# OrbiMote_v0_1.net
KiCad netlist of a schematic drawn in EAGLE
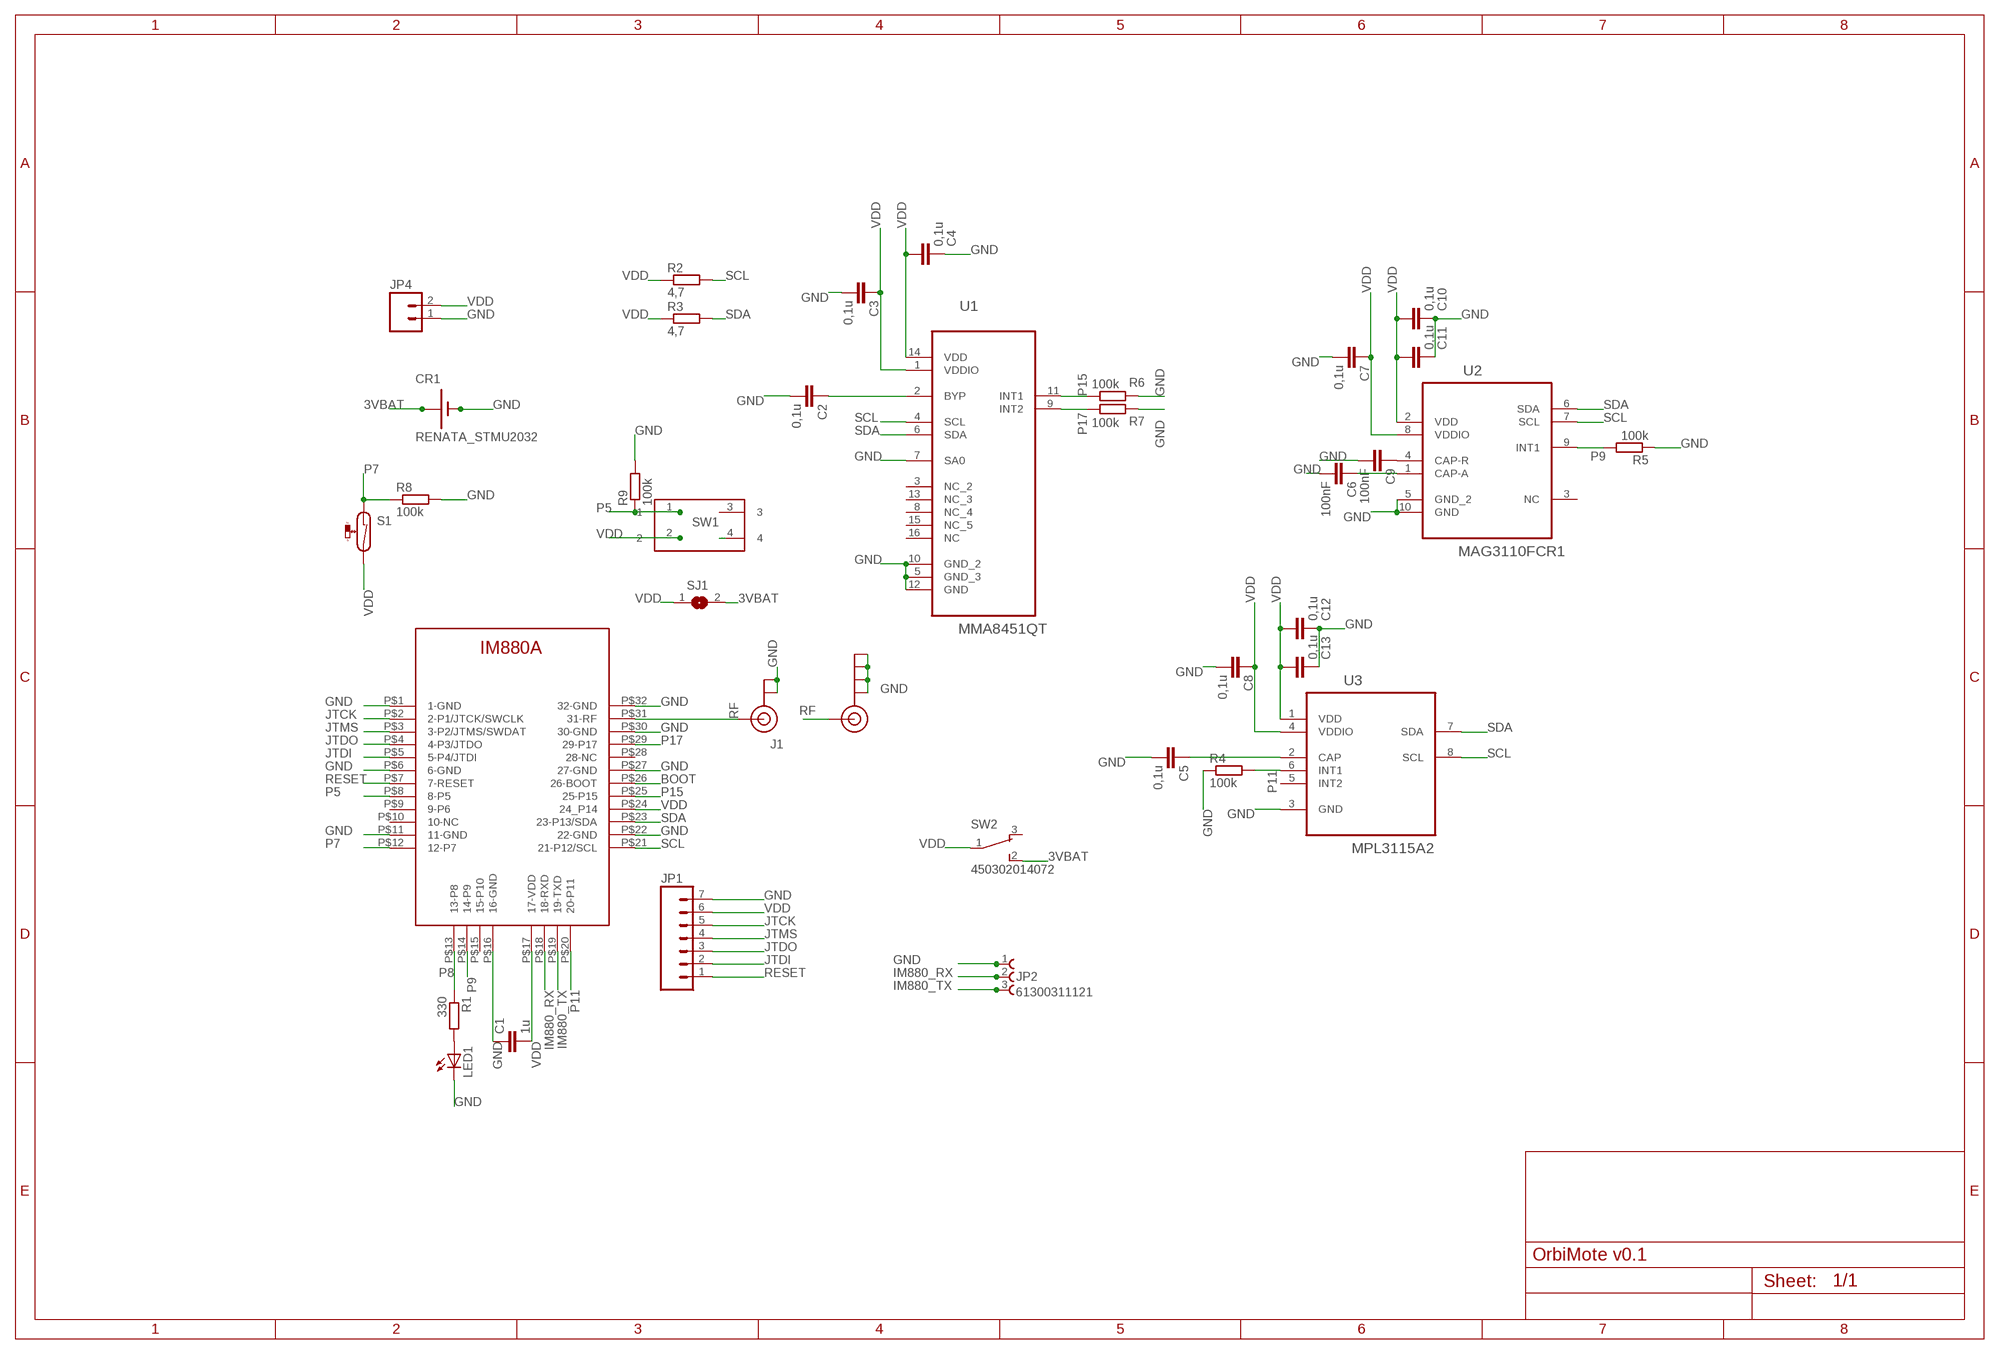
[diagram p0: schematic, sheet 1]

(export (version "E")
  (design (tool "Eeschema 10.0.6"))
  (components
    (comp (ref "C1")
      (value "1u")
      (footprint "eagle-import:C0603")
      (libsource (lib "eagle-import") (part "resistor_C-EUC0603"))
    )
    (comp (ref "C2")
      (value "0,1u")
      (footprint "eagle-import:C0603")
      (libsource (lib "eagle-import") (part "C-EUC0603"))
    )
    (comp (ref "C3")
      (value "0,1u")
      (footprint "eagle-import:C0603")
      (libsource (lib "eagle-import") (part "C-EUC0603"))
    )
    (comp (ref "C4")
      (value "0,1u")
      (footprint "eagle-import:C0603")
      (libsource (lib "eagle-import") (part "C-EUC0603"))
    )
    (comp (ref "C5")
      (value "0,1u")
      (footprint "eagle-import:C0603")
      (libsource (lib "eagle-import") (part "C-EUC0603"))
    )
    (comp (ref "C6")
      (value "100nF")
      (footprint "eagle-import:C0603")
      (libsource (lib "eagle-import") (part "C-EUC0603"))
    )
    (comp (ref "C7")
      (value "0,1u")
      (footprint "eagle-import:C0603")
      (libsource (lib "eagle-import") (part "C-EUC0603"))
    )
    (comp (ref "C8")
      (value "0,1u")
      (footprint "eagle-import:C0603")
      (libsource (lib "eagle-import") (part "C-EUC0603"))
    )
    (comp (ref "C9")
      (value "100nF")
      (footprint "eagle-import:C0603")
      (libsource (lib "eagle-import") (part "C-EUC0603"))
    )
    (comp (ref "C10")
      (value "0,1u")
      (footprint "eagle-import:C0603")
      (libsource (lib "eagle-import") (part "C-EUC0603"))
    )
    (comp (ref "C11")
      (value "0,1u")
      (footprint "eagle-import:C0603")
      (libsource (lib "eagle-import") (part "C-EUC0603"))
    )
    (comp (ref "C12")
      (value "0,1u")
      (footprint "eagle-import:C0603")
      (libsource (lib "eagle-import") (part "C-EUC0603"))
    )
    (comp (ref "C13")
      (value "0,1u")
      (footprint "eagle-import:C0603")
      (libsource (lib "eagle-import") (part "C-EUC0603"))
    )
    (comp (ref "CR1")
      (value "RENATA_STMU2032")
      (footprint "eagle-import:SMTU2032")
      (libsource (lib "eagle-import") (part "RENATA_STMU2032"))
    )
    (comp (ref "IM1")
      (value "IM880A")
      (footprint "eagle-import:IM880A")
      (libsource (lib "eagle-import") (part "IM880A"))
    )
    (comp (ref "J$1")
      (value "SMA_EDGE")
      (footprint "eagle-import:SMA-EDGE")
      (libsource (lib "eagle-import") (part "SMA_EDGE"))
    )
    (comp (ref "J1")
      (value "U.FL")
      (footprint "eagle-import:U.FL")
      (libsource (lib "eagle-import") (part "U.FL"))
    )
    (comp (ref "JP1")
      (value "M07")
      (footprint "eagle-import:1X07")
      (libsource (lib "eagle-import") (part "M07"))
    )
    (comp (ref "JP2")
      (value "61300311121")
      (footprint "eagle-import:61300311121")
      (libsource (lib "eagle-import") (part "61300311121"))
    )
    (comp (ref "JP4")
      (value "M02JST-PTH-VERT")
      (footprint "eagle-import:JST-2-PTH-VERT")
      (libsource (lib "eagle-import") (part "M02JST-PTH-VERT"))
    )
    (comp (ref "LED1")
      (value "LEDCHIPLED_0603")
      (footprint "eagle-import:CHIPLED_0603")
      (libsource (lib "eagle-import") (part "LEDCHIPLED_0603"))
    )
    (comp (ref "R1")
      (value "330")
      (footprint "eagle-import:R0603")
      (libsource (lib "eagle-import") (part "R-EU_R0603"))
    )
    (comp (ref "R2")
      (value "4,7")
      (footprint "eagle-import:R0603")
      (libsource (lib "eagle-import") (part "R-EU_R0603"))
    )
    (comp (ref "R3")
      (value "4,7")
      (footprint "eagle-import:R0603")
      (libsource (lib "eagle-import") (part "R-EU_R0603"))
    )
    (comp (ref "R4")
      (value "100k")
      (footprint "eagle-import:R0603")
      (libsource (lib "eagle-import") (part "R-EU_R0603"))
    )
    (comp (ref "R5")
      (value "100k")
      (footprint "eagle-import:R0603")
      (libsource (lib "eagle-import") (part "R-EU_R0603"))
    )
    (comp (ref "R6")
      (value "100k")
      (footprint "eagle-import:R0603")
      (libsource (lib "eagle-import") (part "R-EU_R0603"))
    )
    (comp (ref "R7")
      (value "100k")
      (footprint "eagle-import:R0603")
      (libsource (lib "eagle-import") (part "R-EU_R0603"))
    )
    (comp (ref "R8")
      (value "100k")
      (footprint "eagle-import:R0603")
      (libsource (lib "eagle-import") (part "R-EU_R0603"))
    )
    (comp (ref "R9")
      (value "100k")
      (footprint "eagle-import:R0603")
      (libsource (lib "eagle-import") (part "R-EU_R0603"))
    )
    (comp (ref "S1")
      (value "REED-SWITCH-CT10-1530-G1")
      (footprint "eagle-import:CT10-G1")
      (fields (field (name "MF") "COTO TECHNOLOGY") (field (name "MPN") "CT10-1530-G1"))
      (libsource (lib "eagle-import") (part "REED-SWITCH-CT10-1530-G1"))
    )
    (comp (ref "SJ1") (value "SJ") (footprint "eagle-import:SJ") (libsource (lib "eagle-import") (part "SJ")))
    (comp (ref "SW1")
      (value "430152043826")
      (footprint "eagle-import:430152043826")
      (libsource (lib "eagle-import") (part "430152043826"))
    )
    (comp (ref "SW2")
      (value "450302014072")
      (footprint "eagle-import:450302014072")
      (libsource (lib "eagle-import") (part "450302014072"))
    )
    (comp (ref "U1")
      (value "MMA8451QT")
      (footprint "eagle-import:QFN50P300X300X100-16N")
      (fields (field (name "MPN") "MMA8451QT "))
      (libsource (lib "eagle-import") (part "MMA8451QT"))
    )
    (comp (ref "U2")
      (value "MAG3110FCR1")
      (footprint "eagle-import:DFN200X200X90-10N")
      (libsource (lib "eagle-import") (part "MAG3110FCR1"))
    )
    (comp (ref "U3")
      (value "MPL3115A2")
      (footprint "eagle-import:DFN300X500X120-8N")
      (libsource (lib "eagle-import") (part "MPL3115A2"))
    )
  )
  (nets
    (net (code "1") (name "/3VBAT") (class "Default")
      (node (ref "CR1") (pin "+") (pinfunction "3VBAT_+") (pintype "passive"))
      (node (ref "SJ1") (pin "2") (pinfunction "2_2") (pintype "passive"))
      (node (ref "SW2") (pin "2") (pinfunction "2_2") (pintype "passive"))
    )
    (net (code "2") (name "/BOOT") (class "Default")
      (node (ref "IM1") (pin "P$26") (pinfunction "26-BOOT_P$26") (pintype "bidirectional"))
    )
    (net (code "3") (name "/GND") (class "Default")
      (node (ref "C1") (pin "1") (pinfunction "1_1") (pintype "passive"))
      (node (ref "C10") (pin "2") (pinfunction "2_2") (pintype "passive"))
      (node (ref "C11") (pin "2") (pinfunction "2_2") (pintype "passive"))
      (node (ref "C12") (pin "2") (pinfunction "2_2") (pintype "passive"))
      (node (ref "C13") (pin "2") (pinfunction "2_2") (pintype "passive"))
      (node (ref "C2") (pin "2") (pinfunction "2_2") (pintype "passive"))
      (node (ref "C3") (pin "2") (pinfunction "2_2") (pintype "passive"))
      (node (ref "C4") (pin "2") (pinfunction "2_2") (pintype "passive"))
      (node (ref "C5") (pin "2") (pinfunction "2_2") (pintype "passive"))
      (node (ref "C6") (pin "2") (pinfunction "2_2") (pintype "passive"))
      (node (ref "C7") (pin "2") (pinfunction "2_2") (pintype "passive"))
      (node (ref "C8") (pin "2") (pinfunction "2_2") (pintype "passive"))
      (node (ref "C9") (pin "2") (pinfunction "2_2") (pintype "passive"))
      (node (ref "CR1") (pin "-") (pinfunction "-_-") (pintype "passive"))
      (node (ref "IM1") (pin "P$1") (pinfunction "1-GND_P$1") (pintype "bidirectional"))
      (node (ref "IM1") (pin "P$11") (pinfunction "11-GND_P$11") (pintype "bidirectional"))
      (node (ref "IM1") (pin "P$16") (pinfunction "16-GND_P$16") (pintype "bidirectional"))
      (node (ref "IM1") (pin "P$22") (pinfunction "22-GND_P$22") (pintype "bidirectional"))
      (node (ref "IM1") (pin "P$27") (pinfunction "27-GND_P$27") (pintype "bidirectional"))
      (node (ref "IM1") (pin "P$30") (pinfunction "30-GND_P$30") (pintype "bidirectional"))
      (node (ref "IM1") (pin "P$32") (pinfunction "32-GND_P$32") (pintype "bidirectional"))
      (node (ref "IM1") (pin "P$6") (pinfunction "6-GND_P$6") (pintype "bidirectional"))
      (node (ref "J$1") (pin "GND@0") (pinfunction "GND_GND@0") (pintype "bidirectional"))
      (node (ref "J$1") (pin "GND@1") (pinfunction "GND_GND@1") (pintype "bidirectional"))
      (node (ref "J$1") (pin "GND@2") (pinfunction "GND_GND@2") (pintype "bidirectional"))
      (node (ref "J$1") (pin "GND@3") (pinfunction "GND_GND@3") (pintype "bidirectional"))
      (node (ref "J1") (pin "P$1") (pinfunction "GND_P$1") (pintype "bidirectional"))
      (node (ref "J1") (pin "P$2") (pinfunction "GND_P$2") (pintype "bidirectional"))
      (node (ref "JP1") (pin "7") (pinfunction "7_7") (pintype "passive"))
      (node (ref "JP2") (pin "1") (pinfunction "1_1") (pintype "passive"))
      (node (ref "JP4") (pin "1") (pinfunction "1_1") (pintype "passive"))
      (node (ref "LED1") (pin "C") (pinfunction "C_C") (pintype "passive"))
      (node (ref "R4") (pin "1") (pinfunction "1_1") (pintype "passive"))
      (node (ref "R5") (pin "1") (pinfunction "1_1") (pintype "passive"))
      (node (ref "R6") (pin "1") (pinfunction "1_1") (pintype "passive"))
      (node (ref "R7") (pin "1") (pinfunction "1_1") (pintype "passive"))
      (node (ref "R8") (pin "2") (pinfunction "2_2") (pintype "passive"))
      (node (ref "R9") (pin "2") (pinfunction "2_2") (pintype "passive"))
      (node (ref "U1") (pin "10") (pinfunction "GND_2_10") (pintype "passive"))
      (node (ref "U1") (pin "12") (pinfunction "GND_12") (pintype "passive"))
      (node (ref "U1") (pin "5") (pinfunction "GND_3_5") (pintype "passive"))
      (node (ref "U1") (pin "7") (pinfunction "SA0_7") (pintype "input"))
      (node (ref "U2") (pin "10") (pinfunction "GND_10") (pintype "power_in"))
      (node (ref "U2") (pin "5") (pinfunction "GND_2_5") (pintype "power_in"))
      (node (ref "U3") (pin "3") (pinfunction "GND_3") (pintype "power_in"))
    )
    (net (code "4") (name "/IM880_RX") (class "Default")
      (node (ref "IM1") (pin "P$18") (pinfunction "18-RXD_P$18") (pintype "bidirectional"))
      (node (ref "JP2") (pin "2") (pinfunction "2_2") (pintype "passive"))
    )
    (net (code "5") (name "/IM880_TX") (class "Default")
      (node (ref "IM1") (pin "P$19") (pinfunction "19-TXD_P$19") (pintype "bidirectional"))
      (node (ref "JP2") (pin "3") (pinfunction "3_3") (pintype "passive"))
    )
    (net (code "6") (name "/JTCK") (class "Default")
      (node (ref "IM1") (pin "P$2") (pinfunction "2-P1/JTCK/SWCLK_P$2") (pintype "bidirectional"))
      (node (ref "JP1") (pin "5") (pinfunction "5_5") (pintype "passive"))
    )
    (net (code "7") (name "/JTDI") (class "Default")
      (node (ref "IM1") (pin "P$5") (pinfunction "5-P4/JTDI_P$5") (pintype "bidirectional"))
      (node (ref "JP1") (pin "2") (pinfunction "2_2") (pintype "passive"))
    )
    (net (code "8") (name "/JTDO") (class "Default")
      (node (ref "IM1") (pin "P$4") (pinfunction "4-P3/JTDO_P$4") (pintype "bidirectional"))
      (node (ref "JP1") (pin "3") (pinfunction "3_3") (pintype "passive"))
    )
    (net (code "9") (name "/JTMS") (class "Default")
      (node (ref "IM1") (pin "P$3") (pinfunction "3-P2/JTMS/SWDAT_P$3") (pintype "bidirectional"))
      (node (ref "JP1") (pin "4") (pinfunction "4_4") (pintype "passive"))
    )
    (net (code "10") (name "/P5") (class "Default")
      (node (ref "IM1") (pin "P$8") (pinfunction "8-P5_P$8") (pintype "bidirectional"))
      (node (ref "R9") (pin "1") (pinfunction "1_1") (pintype "passive"))
      (node (ref "SW1") (pin "1") (pinfunction "1_1") (pintype "bidirectional"))
    )
    (net (code "11") (name "/P7") (class "Default")
      (node (ref "IM1") (pin "P$12") (pinfunction "12-P7_P$12") (pintype "bidirectional"))
      (node (ref "R8") (pin "1") (pinfunction "1_1") (pintype "passive"))
      (node (ref "S1") (pin "1") (pinfunction "1_1") (pintype "passive"))
    )
    (net (code "12") (name "/P8") (class "Default")
      (node (ref "IM1") (pin "P$13") (pinfunction "13-P8_P$13") (pintype "bidirectional"))
      (node (ref "R1") (pin "1") (pinfunction "1_1") (pintype "passive"))
    )
    (net (code "13") (name "/P9") (class "Default")
      (node (ref "IM1") (pin "P$14") (pinfunction "14-P9_P$14") (pintype "bidirectional"))
      (node (ref "R5") (pin "2") (pinfunction "2_2") (pintype "passive"))
      (node (ref "U2") (pin "9") (pinfunction "INT1_9") (pintype "output"))
    )
    (net (code "14") (name "/P11") (class "Default")
      (node (ref "IM1") (pin "P$20") (pinfunction "20-P11_P$20") (pintype "bidirectional"))
      (node (ref "R4") (pin "2") (pinfunction "2_2") (pintype "passive"))
      (node (ref "U3") (pin "6") (pinfunction "INT1_6") (pintype "passive"))
    )
    (net (code "15") (name "/P15") (class "Default")
      (node (ref "IM1") (pin "P$25") (pinfunction "25-P15_P$25") (pintype "bidirectional"))
      (node (ref "R6") (pin "2") (pinfunction "2_2") (pintype "passive"))
      (node (ref "U1") (pin "11") (pinfunction "INT1_11") (pintype "output"))
    )
    (net (code "16") (name "/P17") (class "Default")
      (node (ref "IM1") (pin "P$29") (pinfunction "29-P17_P$29") (pintype "bidirectional"))
      (node (ref "R7") (pin "2") (pinfunction "2_2") (pintype "passive"))
      (node (ref "U1") (pin "9") (pinfunction "INT2_9") (pintype "output"))
    )
    (net (code "17") (name "/RESET") (class "Default")
      (node (ref "IM1") (pin "P$7") (pinfunction "7-RESET_P$7") (pintype "bidirectional"))
      (node (ref "JP1") (pin "1") (pinfunction "1_1") (pintype "passive"))
    )
    (net (code "18") (name "/RF") (class "Default")
      (node (ref "IM1") (pin "P$31") (pinfunction "31-RF_P$31") (pintype "bidirectional"))
      (node (ref "J$1") (pin "SIG") (pinfunction "SIGNAL_SIG") (pintype "bidirectional"))
      (node (ref "J1") (pin "P$3") (pinfunction "SIGNAL_P$3") (pintype "bidirectional"))
    )
    (net (code "19") (name "/SCL") (class "Default")
      (node (ref "IM1") (pin "P$21") (pinfunction "21-P12/SCL_P$21") (pintype "bidirectional"))
      (node (ref "R2") (pin "2") (pinfunction "2_2") (pintype "passive"))
      (node (ref "U1") (pin "4") (pinfunction "SCL_4") (pintype "passive"))
      (node (ref "U2") (pin "7") (pinfunction "SCL_7") (pintype "passive"))
      (node (ref "U3") (pin "8") (pinfunction "SCL_8") (pintype "input"))
    )
    (net (code "20") (name "/SDA") (class "Default")
      (node (ref "IM1") (pin "P$23") (pinfunction "23-P13/SDA_P$23") (pintype "bidirectional"))
      (node (ref "R3") (pin "2") (pinfunction "2_2") (pintype "passive"))
      (node (ref "U1") (pin "6") (pinfunction "SDA_6") (pintype "passive"))
      (node (ref "U2") (pin "6") (pinfunction "SDA_6") (pintype "passive"))
      (node (ref "U3") (pin "7") (pinfunction "SDA_7") (pintype "bidirectional"))
    )
    (net (code "21") (name "/VDD") (class "Default")
      (node (ref "C1") (pin "2") (pinfunction "2_2") (pintype "passive"))
      (node (ref "C10") (pin "1") (pinfunction "1_1") (pintype "passive"))
      (node (ref "C11") (pin "1") (pinfunction "1_1") (pintype "passive"))
      (node (ref "C12") (pin "1") (pinfunction "1_1") (pintype "passive"))
      (node (ref "C13") (pin "1") (pinfunction "1_1") (pintype "passive"))
      (node (ref "C3") (pin "1") (pinfunction "1_1") (pintype "passive"))
      (node (ref "C4") (pin "1") (pinfunction "1_1") (pintype "passive"))
      (node (ref "C7") (pin "1") (pinfunction "1_1") (pintype "passive"))
      (node (ref "C8") (pin "1") (pinfunction "1_1") (pintype "passive"))
      (node (ref "IM1") (pin "P$17") (pinfunction "17-VDD_P$17") (pintype "bidirectional"))
      (node (ref "IM1") (pin "P$24") (pinfunction "24_P14_P$24") (pintype "bidirectional"))
      (node (ref "JP1") (pin "6") (pinfunction "6_6") (pintype "passive"))
      (node (ref "JP4") (pin "2") (pinfunction "2_2") (pintype "passive"))
      (node (ref "R2") (pin "1") (pinfunction "1_1") (pintype "passive"))
      (node (ref "R3") (pin "1") (pinfunction "1_1") (pintype "passive"))
      (node (ref "S1") (pin "2") (pinfunction "2_2") (pintype "passive"))
      (node (ref "SJ1") (pin "1") (pinfunction "1_1") (pintype "passive"))
      (node (ref "SW1") (pin "2") (pinfunction "2_2") (pintype "bidirectional"))
      (node (ref "SW2") (pin "1") (pinfunction "1_1") (pintype "passive"))
      (node (ref "U1") (pin "1") (pinfunction "VDDIO_1") (pintype "power_in"))
      (node (ref "U1") (pin "14") (pinfunction "VDD_14") (pintype "power_in"))
      (node (ref "U2") (pin "2") (pinfunction "VDD_2") (pintype "power_in"))
      (node (ref "U2") (pin "8") (pinfunction "VDDIO_8") (pintype "power_in"))
      (node (ref "U3") (pin "1") (pinfunction "VDD_1") (pintype "power_in"))
      (node (ref "U3") (pin "4") (pinfunction "VDDIO_4") (pintype "power_in"))
    )
    (net (code "22") (name "Net-(LED1-PadA)") (class "Default")
      (node (ref "LED1") (pin "A") (pinfunction "A_A") (pintype "passive"))
      (node (ref "R1") (pin "2") (pinfunction "2_2") (pintype "passive"))
    )
    (net (code "23") (name "Net-(U1-BYP)") (class "Default")
      (node (ref "C2") (pin "1") (pinfunction "1_1") (pintype "passive"))
      (node (ref "U1") (pin "2") (pinfunction "BYP_2") (pintype "input"))
    )
    (net (code "24") (name "Net-(U2-CAP-A)") (class "Default")
      (node (ref "C6") (pin "1") (pinfunction "1_1") (pintype "passive"))
      (node (ref "U2") (pin "1") (pinfunction "CAP-A_1") (pintype "passive"))
    )
    (net (code "25") (name "Net-(U2-CAP-R)") (class "Default")
      (node (ref "C9") (pin "1") (pinfunction "1_1") (pintype "passive"))
      (node (ref "U2") (pin "4") (pinfunction "CAP-R_4") (pintype "passive"))
    )
    (net (code "26") (name "Net-(U3-CAP)") (class "Default")
      (node (ref "C5") (pin "1") (pinfunction "1_1") (pintype "passive"))
      (node (ref "U3") (pin "2") (pinfunction "CAP_2") (pintype "passive"))
    )
    (net (code "27") (name "unconnected-(IM1-9-P6-PadP$9)") (class "Default")
      (node (ref "IM1") (pin "P$9") (pinfunction "9-P6_P$9") (pintype "bidirectional"))
    )
    (net (code "28") (name "unconnected-(IM1-10-NC-PadP$10)") (class "Default")
      (node (ref "IM1") (pin "P$10") (pinfunction "10-NC_P$10") (pintype "bidirectional"))
    )
    (net (code "29") (name "unconnected-(IM1-15-P10-PadP$15)") (class "Default")
      (node (ref "IM1") (pin "P$15") (pinfunction "15-P10_P$15") (pintype "bidirectional"))
    )
    (net (code "30") (name "unconnected-(IM1-28-NC-PadP$28)") (class "Default")
      (node (ref "IM1") (pin "P$28") (pinfunction "28-NC_P$28") (pintype "bidirectional"))
    )
    (net (code "31") (name "unconnected-(SW1-Pad3)") (class "Default")
      (node (ref "SW1") (pin "3") (pinfunction "3_3") (pintype "bidirectional"))
    )
    (net (code "32") (name "unconnected-(SW1-Pad4)") (class "Default")
      (node (ref "SW1") (pin "4") (pinfunction "4_4") (pintype "bidirectional"))
    )
    (net (code "33") (name "unconnected-(SW2-Pad3)") (class "Default")
      (node (ref "SW2") (pin "3") (pinfunction "3_3") (pintype "passive"))
    )
    (net (code "34") (name "unconnected-(U1-NC-Pad16)") (class "Default")
      (node (ref "U1") (pin "16") (pinfunction "NC_16") (pintype "no_connect"))
    )
    (net (code "35") (name "unconnected-(U1-NC_2-Pad3)") (class "Default")
      (node (ref "U1") (pin "3") (pinfunction "NC_2_3") (pintype "no_connect"))
    )
    (net (code "36") (name "unconnected-(U1-NC_3-Pad13)") (class "Default")
      (node (ref "U1") (pin "13") (pinfunction "NC_3_13") (pintype "no_connect"))
    )
    (net (code "37") (name "unconnected-(U1-NC_4-Pad8)") (class "Default")
      (node (ref "U1") (pin "8") (pinfunction "NC_4_8") (pintype "no_connect"))
    )
    (net (code "38") (name "unconnected-(U1-NC_5-Pad15)") (class "Default")
      (node (ref "U1") (pin "15") (pinfunction "NC_5_15") (pintype "no_connect"))
    )
    (net (code "39") (name "unconnected-(U2-NC-Pad3)") (class "Default")
      (node (ref "U2") (pin "3") (pinfunction "NC_3") (pintype "no_connect"))
    )
    (net (code "40") (name "unconnected-(U3-INT2-Pad5)") (class "Default")
      (node (ref "U3") (pin "5") (pinfunction "INT2_5") (pintype "passive"))
    )
  )
)
